# dimmer_sensor.net
KiCad netlist of a schematic drawn in Altium Designer
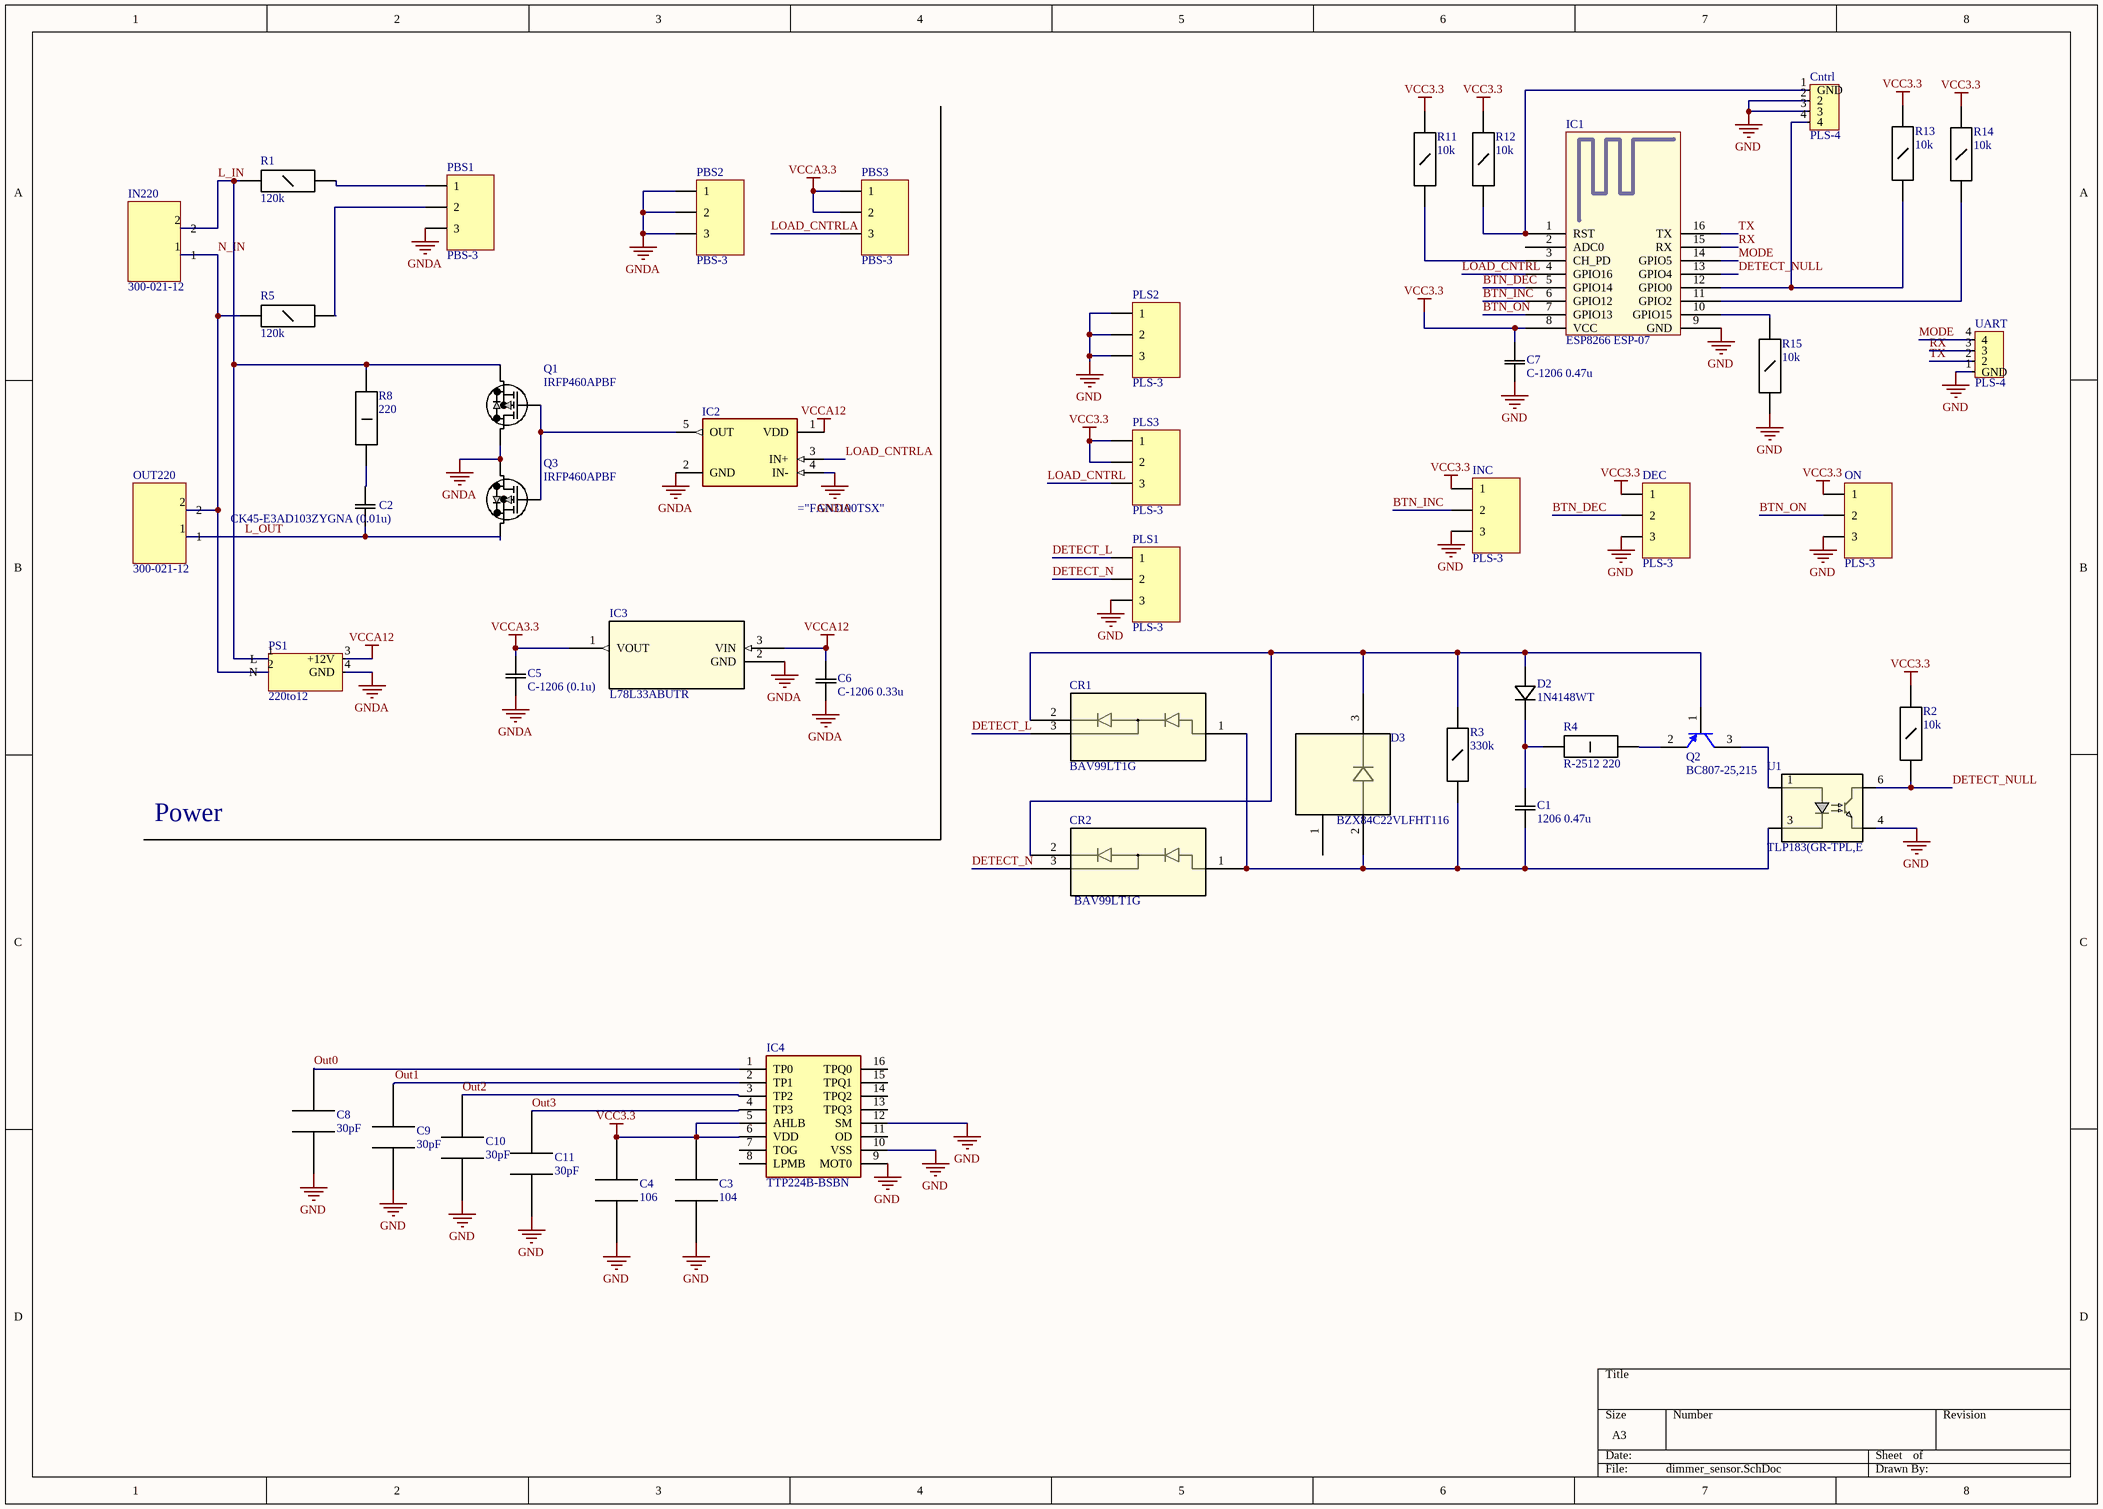
[diagram p0: dimmer_sensor.SchDoc]

(export (version "E")
  (design (tool "Eeschema 10.0.6"))
  (components
    (comp (ref "C1")
      (value "1206 0.47u")
      (footprint "CAP_X7R_1206_AVX")
      (description "No Description Available")
      (fields
        (field (name "MANUFACTURER_PART_NUMBER") "12061C104KAT2A")
        (field (name "COPYRIGHT") "Copyright (C) 2018 Accelerated Designs. All rights reserved")
      )
      (libsource (lib "diplom") (part "C-1206"))
    )
    (comp (ref "C2")
      (value "CK45-E3AD103ZYGNA (0.01u)")
      (footprint "CAP_CK45E3103_TDK")
      (description "No Description Available")
      (fields
        (field (name "MANUFACTURER_PART_NUMBER") "CK45-E3AD103ZYGNA")
        (field (name "COPYRIGHT") "Copyright (C) 2018 Accelerated Designs. All rights reserved")
      )
      (libsource (lib "diplom") (part "CK45-E3AD103ZYGNA"))
    )
    (comp (ref "C3")
      (value "104")
      (footprint "0805")
      (description "0805 ceramic capacitor")
      (libsource (lib "diplom") (part "C0805"))
    )
    (comp (ref "C4")
      (value "106")
      (footprint "0805")
      (description "0805 ceramic capacitor")
      (libsource (lib "diplom") (part "C0805"))
    )
    (comp (ref "C5")
      (value "C-1206 (0.1u)")
      (footprint "CAP_X7R_1206_AVX")
      (description "No Description Available")
      (fields
        (field (name "MANUFACTURER_PART_NUMBER") "12061C104KAT2A")
        (field (name "COPYRIGHT") "Copyright (C) 2018 Accelerated Designs. All rights reserved")
      )
      (libsource (lib "diplom") (part "C-1206"))
    )
    (comp (ref "C6")
      (value "C-1206 0.33u")
      (footprint "CAP_X7R_1206_AVX")
      (description "No Description Available")
      (fields
        (field (name "MANUFACTURER_PART_NUMBER") "12061C104KAT2A")
        (field (name "COPYRIGHT") "Copyright (C) 2018 Accelerated Designs. All rights reserved")
      )
      (libsource (lib "diplom") (part "C-1206"))
    )
    (comp (ref "C7")
      (value "C-1206 0.47u")
      (footprint "CAP_X7R_1206_AVX")
      (description "No Description Available")
      (fields
        (field (name "MANUFACTURER_PART_NUMBER") "12061C104KAT2A")
        (field (name "COPYRIGHT") "Copyright (C) 2018 Accelerated Designs. All rights reserved")
      )
      (libsource (lib "diplom") (part "C-1206"))
    )
    (comp (ref "C8")
      (value "30pF")
      (footprint "0805")
      (description "0805 ceramic capacitor")
      (libsource (lib "diplom") (part "C0805"))
    )
    (comp (ref "C9")
      (value "30pF")
      (footprint "0805")
      (description "0805 ceramic capacitor")
      (libsource (lib "diplom") (part "C0805"))
    )
    (comp (ref "C10")
      (value "30pF")
      (footprint "0805")
      (description "0805 ceramic capacitor")
      (libsource (lib "diplom") (part "C0805"))
    )
    (comp (ref "C11")
      (value "30pF")
      (footprint "0805")
      (description "0805 ceramic capacitor")
      (libsource (lib "diplom") (part "C0805"))
    )
    (comp (ref "Cntrl") (value "PLS-4") (footprint "PLS-4") (libsource (lib "diplom") (part "PLS-4")))
    (comp (ref "CR1")
      (value "BAV99LT1G")
      (footprint "SOT-23_TO-236_318-08_ONS")
      (description "No Description Available")
      (fields (field (name "COPYRIGHT") "Copyright (C) 2018 Accelerated Designs. All rights reserved"))
      (libsource (lib "diplom") (part "BAV99LT1G"))
    )
    (comp (ref "CR2")
      (value "BAV99LT1G")
      (footprint "SOT-23_TO-236_318-08_ONS")
      (description "No Description Available")
      (fields (field (name "COPYRIGHT") "Copyright (C) 2018 Accelerated Designs. All rights reserved"))
      (libsource (lib "diplom") (part "BAV99LT1G"))
    )
    (comp (ref "D2")
      (value "1N4148WT")
      (footprint "CR_SOD-523F_ONS")
      (description "No Description Available")
      (fields (field (name "COPYRIGHT") "Copyright (C) 2018 Accelerated Designs. All rights reserved"))
      (libsource (lib "diplom") (part "1N4148WT"))
    )
    (comp (ref "D3")
      (value "BZX84C22VLFHT116")
      (footprint "TRANS_BZX84_ROM")
      (description "No Description Available")
      (fields (field (name "COPYRIGHT") "Copyright (C) 2018 Accelerated Designs. All rights reserved"))
      (libsource (lib "diplom") (part "BZX84C22VLFHT116"))
    )
    (comp (ref "DEC") (value "PLS-3") (footprint "PLS-3") (libsource (lib "diplom") (part "PLS-3")))
    (comp (ref "IC1")
      (value "ESP8266 ESP-07")
      (footprint "ESP8266 ESP-07")
      (libsource (lib "diplom") (part "ESP8266 ESP-07"))
    )
    (comp (ref "IC2")
      (value "FAN3100TSX")
      (footprint "ON_Semi_527AH_0")
      (libsource (lib "diplom") (part "FAN3100TSX"))
    )
    (comp (ref "IC3")
      (value "L78L33ABUTR")
      (footprint "SOT-89_STM")
      (description "No Description Available")
      (fields (field (name "COPYRIGHT") "Copyright (C) 2018 Accelerated Designs. All rights reserved"))
      (libsource (lib "diplom") (part "L78L33ABUTR"))
    )
    (comp (ref "IC4")
      (value "TTP224B-BSBN")
      (footprint "SOP64P600X175-16N")
      (description "Integrated Circuit")
      (libsource (lib "diplom") (part "TTP224B-BSBN"))
    )
    (comp (ref "IN220")
      (value "300-021-12")
      (footprint "300-021-12")
      (libsource (lib "diplom") (part "300-021-12"))
    )
    (comp (ref "INC") (value "PLS-3") (footprint "PLS-3") (libsource (lib "diplom") (part "PLS-3")))
    (comp (ref "ON") (value "PLS-3") (footprint "PLS-3") (libsource (lib "diplom") (part "PLS-3")))
    (comp (ref "OUT220")
      (value "300-021-12")
      (footprint "300-021-12")
      (libsource (lib "diplom") (part "300-021-12"))
    )
    (comp (ref "PBS1") (value "PBS-3") (footprint "PBS-3") (libsource (lib "diplom") (part "PBS-3")))
    (comp (ref "PBS2") (value "PBS-3") (footprint "PBS-3") (libsource (lib "diplom") (part "PBS-3")))
    (comp (ref "PBS3") (value "PBS-3") (footprint "PBS-3") (libsource (lib "diplom") (part "PBS-3")))
    (comp (ref "PLS1") (value "PLS-3") (footprint "PLS-3") (libsource (lib "diplom") (part "PLS-3")))
    (comp (ref "PLS2") (value "PLS-3") (footprint "PLS-3") (libsource (lib "diplom") (part "PLS-3")))
    (comp (ref "PLS3") (value "PLS-3") (footprint "PLS-3") (libsource (lib "diplom") (part "PLS-3")))
    (comp (ref "PS1") (value "220to12") (footprint "220to12") (libsource (lib "diplom") (part "220to12")))
    (comp (ref "Q1")
      (value "IRFP460APBF")
      (footprint "TO-247AC_VIS")
      (description "No Description Available")
      (fields (field (name "COPYRIGHT") "Copyright (C) 2018 Accelerated Designs. All rights reserved"))
      (libsource (lib "diplom") (part "IRFP460APBF"))
    )
    (comp (ref "Q2")
      (value "BC807-25,215")
      (footprint "SOT23_BC807_NEX")
      (description "No Description Available")
      (fields (field (name "COPYRIGHT") "Copyright (C) 2016 Accelerated Designs. All rights reserved"))
      (libsource (lib "diplom") (part "BC807-25,215"))
    )
    (comp (ref "Q3")
      (value "IRFP460APBF")
      (footprint "TO-247AC_VIS")
      (description "No Description Available")
      (fields (field (name "COPYRIGHT") "Copyright (C) 2018 Accelerated Designs. All rights reserved"))
      (libsource (lib "diplom") (part "IRFP460APBF"))
    )
    (comp (ref "R1")
      (value "120k")
      (footprint "CAP_X7R_1206_AVX")
      (description "R-1206")
      (libsource (lib "diplom") (part "R-1206"))
    )
    (comp (ref "R2")
      (value "10k")
      (footprint "CAP_X7R_1206_AVX")
      (description "R-1206")
      (libsource (lib "diplom") (part "R-1206"))
    )
    (comp (ref "R3")
      (value "330k")
      (footprint "CAP_X7R_1206_AVX")
      (description "R-1206")
      (libsource (lib "diplom") (part "R-1206"))
    )
    (comp (ref "R4")
      (value "R-2512 220")
      (footprint "RES2512_TL_TYCO_TYC")
      (description "No Description Available")
      (fields
        (field (name "MANUFACTURER_PART_NUMBER") "TL3AR033F")
        (field (name "COPYRIGHT") "Copyright (C) 2018 Accelerated Designs. All rights reserved")
      )
      (libsource (lib "diplom") (part "R-2512"))
    )
    (comp (ref "R5")
      (value "120k")
      (footprint "CAP_X7R_1206_AVX")
      (description "R-1206")
      (libsource (lib "diplom") (part "R-1206"))
    )
    (comp (ref "R8")
      (value "220")
      (footprint "RES2512_TL_TYCO_TYC")
      (description "No Description Available")
      (fields
        (field (name "MANUFACTURER_PART_NUMBER") "TL3AR033F")
        (field (name "COPYRIGHT") "Copyright (C) 2018 Accelerated Designs. All rights reserved")
      )
      (libsource (lib "diplom") (part "R-2512"))
    )
    (comp (ref "R11")
      (value "10k")
      (footprint "CAP_X7R_1206_AVX")
      (description "R-1206")
      (libsource (lib "diplom") (part "R-1206"))
    )
    (comp (ref "R12")
      (value "10k")
      (footprint "CAP_X7R_1206_AVX")
      (description "R-1206")
      (libsource (lib "diplom") (part "R-1206"))
    )
    (comp (ref "R13")
      (value "10k")
      (footprint "CAP_X7R_1206_AVX")
      (description "R-1206")
      (libsource (lib "diplom") (part "R-1206"))
    )
    (comp (ref "R14")
      (value "10k")
      (footprint "CAP_X7R_1206_AVX")
      (description "R-1206")
      (libsource (lib "diplom") (part "R-1206"))
    )
    (comp (ref "R15")
      (value "10k")
      (footprint "CAP_X7R_1206_AVX")
      (description "R-1206")
      (libsource (lib "diplom") (part "R-1206"))
    )
    (comp (ref "U1")
      (value "TLP183(GR-TPL,E")
      (footprint "4pin SO6_TOS")
      (description "No Description Available")
      (fields (field (name "COPYRIGHT") "Copyright (C) 2018 Accelerated Designs. All rights reserved"))
      (libsource (lib "diplom") (part "TLP183(GR-TPL,E"))
    )
    (comp (ref "UART") (value "PLS-4") (footprint "PLS-4") (libsource (lib "") (part "PLS-4_1")))
  )
  (nets
    (net (code "1") (name "/BTN_DEC") (class "Default")
      (node (ref "DEC") (pin "2") (pinfunction "2_2") (pintype "passive"))
      (node (ref "IC1") (pin "5") (pinfunction "GPIO14_5") (pintype "passive"))
    )
    (net (code "2") (name "/BTN_INC") (class "Default")
      (node (ref "IC1") (pin "6") (pinfunction "GPIO12_6") (pintype "passive"))
      (node (ref "INC") (pin "2") (pinfunction "2_2") (pintype "passive"))
    )
    (net (code "3") (name "/BTN_ON") (class "Default")
      (node (ref "IC1") (pin "7") (pinfunction "GPIO13_7") (pintype "passive"))
      (node (ref "ON") (pin "2") (pinfunction "2_2") (pintype "passive"))
    )
    (net (code "4") (name "/DETECT_L") (class "Default")
      (node (ref "CR1") (pin "3") (pinfunction "3_3") (pintype "passive"))
      (node (ref "PLS1") (pin "1") (pinfunction "1_1") (pintype "passive"))
    )
    (net (code "5") (name "/DETECT_N") (class "Default")
      (node (ref "CR2") (pin "3") (pinfunction "3_3") (pintype "passive"))
      (node (ref "PLS1") (pin "2") (pinfunction "2_2") (pintype "passive"))
    )
    (net (code "6") (name "/DETECT_NULL") (class "Default")
      (node (ref "IC1") (pin "13") (pinfunction "GPIO4_13") (pintype "passive"))
      (node (ref "R2") (pin "1") (pinfunction "1_1") (pintype "passive"))
      (node (ref "U1") (pin "6") (pinfunction "6_6") (pintype "passive"))
    )
    (net (code "7") (name "/LOAD_CNTRL") (class "Default")
      (node (ref "IC1") (pin "4") (pinfunction "GPIO16_4") (pintype "passive"))
      (node (ref "PLS3") (pin "3") (pinfunction "3_3") (pintype "passive"))
    )
    (net (code "8") (name "/LOAD_CNTRLA") (class "Default")
      (node (ref "IC2") (pin "3") (pinfunction "IN+_3") (pintype "input"))
      (node (ref "PBS3") (pin "3") (pinfunction "3_3") (pintype "passive"))
    )
    (net (code "9") (name "/L_IN") (class "Default")
      (node (ref "IN220") (pin "2") (pinfunction "2_2") (pintype "passive"))
      (node (ref "PS1") (pin "1") (pinfunction "L_1") (pintype "passive"))
      (node (ref "Q1") (pin "3") (pinfunction "S_3") (pintype "passive"))
      (node (ref "R1") (pin "1") (pinfunction "1_1") (pintype "passive"))
      (node (ref "R8") (pin "2") (pinfunction "2_2") (pintype "passive"))
    )
    (net (code "10") (name "/L_OUT") (class "Default")
      (node (ref "C2") (pin "1") (pinfunction "1_1") (pintype "passive"))
      (node (ref "OUT220") (pin "1") (pinfunction "1_1") (pintype "passive"))
      (node (ref "Q3") (pin "3") (pinfunction "S_3") (pintype "passive"))
    )
    (net (code "11") (name "/MODE") (class "Default")
      (node (ref "IC1") (pin "14") (pinfunction "GPIO5_14") (pintype "passive"))
      (node (ref "UART") (pin "4") (pinfunction "4_4") (pintype "passive"))
    )
    (net (code "12") (name "/N_IN") (class "Default")
      (node (ref "IN220") (pin "1") (pinfunction "1_1") (pintype "passive"))
      (node (ref "OUT220") (pin "2") (pinfunction "2_2") (pintype "passive"))
      (node (ref "PS1") (pin "2") (pinfunction "N_2") (pintype "passive"))
      (node (ref "R5") (pin "1") (pinfunction "1_1") (pintype "passive"))
    )
    (net (code "13") (name "/Out0") (class "Default")
      (node (ref "C8") (pin "2") (pinfunction "2_2") (pintype "passive"))
      (node (ref "IC4") (pin "1") (pinfunction "TP0_1") (pintype "passive"))
    )
    (net (code "14") (name "/Out1") (class "Default")
      (node (ref "C9") (pin "2") (pinfunction "2_2") (pintype "passive"))
      (node (ref "IC4") (pin "2") (pinfunction "TP1_2") (pintype "passive"))
    )
    (net (code "15") (name "/Out2") (class "Default")
      (node (ref "C10") (pin "2") (pinfunction "2_2") (pintype "passive"))
      (node (ref "IC4") (pin "3") (pinfunction "TP2_3") (pintype "passive"))
    )
    (net (code "16") (name "/Out3") (class "Default")
      (node (ref "C11") (pin "2") (pinfunction "2_2") (pintype "passive"))
      (node (ref "IC4") (pin "4") (pinfunction "TP3_4") (pintype "passive"))
    )
    (net (code "17") (name "/RX") (class "Default")
      (node (ref "IC1") (pin "15") (pinfunction "RX_15") (pintype "passive"))
      (node (ref "UART") (pin "3") (pinfunction "3_3") (pintype "passive"))
    )
    (net (code "18") (name "/TX") (class "Default")
      (node (ref "IC1") (pin "16") (pinfunction "TX_16") (pintype "passive"))
      (node (ref "UART") (pin "2") (pinfunction "2_2") (pintype "passive"))
    )
    (net (code "19") (name "GND") (class "Default")
      (node (ref "C10") (pin "1") (pinfunction "1_1") (pintype "passive"))
      (node (ref "C11") (pin "1") (pinfunction "1_1") (pintype "passive"))
      (node (ref "C3") (pin "1") (pinfunction "1_1") (pintype "passive"))
      (node (ref "C4") (pin "1") (pinfunction "1_1") (pintype "passive"))
      (node (ref "C7") (pin "1") (pinfunction "1_1") (pintype "passive"))
      (node (ref "C8") (pin "1") (pinfunction "1_1") (pintype "passive"))
      (node (ref "C9") (pin "1") (pinfunction "1_1") (pintype "passive"))
      (node (ref "Cntrl") (pin "2") (pinfunction "2_2") (pintype "passive"))
      (node (ref "Cntrl") (pin "3") (pinfunction "3_3") (pintype "passive"))
      (node (ref "DEC") (pin "3") (pinfunction "3_3") (pintype "passive"))
      (node (ref "IC1") (pin "9") (pinfunction "GND_9") (pintype "passive"))
      (node (ref "IC4") (pin "10") (pinfunction "VSS_10") (pintype "passive"))
      (node (ref "IC4") (pin "12") (pinfunction "SM_12") (pintype "passive"))
      (node (ref "IC4") (pin "9") (pinfunction "MOT0_9") (pintype "passive"))
      (node (ref "INC") (pin "3") (pinfunction "3_3") (pintype "passive"))
      (node (ref "ON") (pin "3") (pinfunction "3_3") (pintype "passive"))
      (node (ref "PLS1") (pin "3") (pinfunction "3_3") (pintype "passive"))
      (node (ref "PLS2") (pin "1") (pinfunction "1_1") (pintype "passive"))
      (node (ref "PLS2") (pin "2") (pinfunction "2_2") (pintype "passive"))
      (node (ref "PLS2") (pin "3") (pinfunction "3_3") (pintype "passive"))
      (node (ref "R15") (pin "1") (pinfunction "1_1") (pintype "passive"))
      (node (ref "U1") (pin "4") (pinfunction "4_4") (pintype "passive"))
      (node (ref "UART") (pin "1") (pinfunction "GND_1") (pintype "passive"))
    )
    (net (code "20") (name "GNDA") (class "Default")
      (node (ref "C5") (pin "1") (pinfunction "1_1") (pintype "passive"))
      (node (ref "C6") (pin "1") (pinfunction "1_1") (pintype "passive"))
      (node (ref "IC2") (pin "2") (pinfunction "GND_2") (pintype "power_in"))
      (node (ref "IC2") (pin "4") (pinfunction "IN-_4") (pintype "input"))
      (node (ref "IC3") (pin "2") (pinfunction "GND_2") (pintype "passive"))
      (node (ref "PBS1") (pin "3") (pinfunction "3_3") (pintype "passive"))
      (node (ref "PBS2") (pin "1") (pinfunction "1_1") (pintype "passive"))
      (node (ref "PBS2") (pin "2") (pinfunction "2_2") (pintype "passive"))
      (node (ref "PBS2") (pin "3") (pinfunction "3_3") (pintype "passive"))
      (node (ref "PS1") (pin "4") (pinfunction "GND_4") (pintype "passive"))
      (node (ref "Q1") (pin "2") (pinfunction "D_2") (pintype "passive"))
      (node (ref "Q3") (pin "2") (pinfunction "D_2") (pintype "passive"))
    )
    (net (code "21") (name "Net-(C1-Pad2)") (class "Default")
      (node (ref "C1") (pin "2") (pinfunction "2_2") (pintype "passive"))
      (node (ref "D2") (pin "1") (pinfunction "1_1") (pintype "passive"))
      (node (ref "R4") (pin "1") (pinfunction "1_1") (pintype "passive"))
    )
    (net (code "22") (name "Net-(C2-Pad2)") (class "Default")
      (node (ref "C2") (pin "2") (pinfunction "2_2") (pintype "passive"))
      (node (ref "R8") (pin "1") (pinfunction "1_1") (pintype "passive"))
    )
    (net (code "23") (name "Net-(Cntrl-GND)") (class "Default")
      (node (ref "Cntrl") (pin "1") (pinfunction "GND_1") (pintype "passive"))
      (node (ref "IC1") (pin "1") (pinfunction "RST_1") (pintype "power_in"))
      (node (ref "R12") (pin "1") (pinfunction "1_1") (pintype "passive"))
    )
    (net (code "24") (name "Net-(D3-1)") (class "Default")
      (node (ref "C1") (pin "1") (pinfunction "1_1") (pintype "passive"))
      (node (ref "CR1") (pin "1") (pinfunction "1_1") (pintype "passive"))
      (node (ref "CR2") (pin "1") (pinfunction "1_1") (pintype "passive"))
      (node (ref "D3") (pin "2") (pinfunction "1_2") (pintype "passive"))
      (node (ref "R3") (pin "1") (pinfunction "1_1") (pintype "passive"))
      (node (ref "U1") (pin "3") (pinfunction "3_3") (pintype "passive"))
    )
    (net (code "25") (name "Net-(IC1-CH_PD)") (class "Default")
      (node (ref "IC1") (pin "3") (pinfunction "CH_PD_3") (pintype "passive"))
      (node (ref "R11") (pin "1") (pinfunction "1_1") (pintype "passive"))
    )
    (net (code "26") (name "Net-(IC1-GPIO0)") (class "Default")
      (node (ref "Cntrl") (pin "4") (pinfunction "4_4") (pintype "passive"))
      (node (ref "IC1") (pin "12") (pinfunction "GPIO0_12") (pintype "passive"))
      (node (ref "R13") (pin "1") (pinfunction "1_1") (pintype "passive"))
    )
    (net (code "27") (name "Net-(IC1-GPIO2)") (class "Default")
      (node (ref "IC1") (pin "11") (pinfunction "GPIO2_11") (pintype "passive"))
      (node (ref "R14") (pin "1") (pinfunction "1_1") (pintype "passive"))
    )
    (net (code "28") (name "Net-(IC1-GPIO15)") (class "Default")
      (node (ref "IC1") (pin "10") (pinfunction "GPIO15_10") (pintype "passive"))
      (node (ref "R15") (pin "2") (pinfunction "2_2") (pintype "passive"))
    )
    (net (code "29") (name "Net-(IC2-OUT)") (class "Default")
      (node (ref "IC2") (pin "5") (pinfunction "OUT_5") (pintype "output"))
      (node (ref "Q1") (pin "1") (pinfunction "G_1") (pintype "passive"))
      (node (ref "Q3") (pin "1") (pinfunction "G_1") (pintype "passive"))
    )
    (net (code "30") (name "Net-(PBS1-Pad1)") (class "Default")
      (node (ref "PBS1") (pin "1") (pinfunction "1_1") (pintype "passive"))
      (node (ref "R1") (pin "2") (pinfunction "2_2") (pintype "passive"))
    )
    (net (code "31") (name "Net-(PBS1-Pad2)") (class "Default")
      (node (ref "PBS1") (pin "2") (pinfunction "2_2") (pintype "passive"))
      (node (ref "R5") (pin "2") (pinfunction "2_2") (pintype "passive"))
    )
    (net (code "32") (name "Net-(Q2-B)") (class "Default")
      (node (ref "CR1") (pin "2") (pinfunction "2_2") (pintype "passive"))
      (node (ref "CR2") (pin "2") (pinfunction "2_2") (pintype "passive"))
      (node (ref "D2") (pin "2") (pinfunction "2_2") (pintype "passive"))
      (node (ref "D3") (pin "3") (pinfunction "3_3") (pintype "passive"))
      (node (ref "Q2") (pin "1") (pinfunction "B_1") (pintype "passive"))
      (node (ref "R3") (pin "2") (pinfunction "2_2") (pintype "passive"))
    )
    (net (code "33") (name "Net-(Q2-C)") (class "Default")
      (node (ref "Q2") (pin "3") (pinfunction "C_3") (pintype "passive"))
      (node (ref "U1") (pin "1") (pinfunction "1_1") (pintype "passive"))
    )
    (net (code "34") (name "Net-(Q2-Pad2)") (class "Default")
      (node (ref "Q2") (pin "2") (pintype "passive"))
      (node (ref "R4") (pin "2") (pinfunction "2_2") (pintype "passive"))
    )
    (net (code "35") (name "VCC3.3") (class "Default")
      (node (ref "C3") (pin "2") (pinfunction "2_2") (pintype "passive"))
      (node (ref "C4") (pin "2") (pinfunction "2_2") (pintype "passive"))
      (node (ref "C7") (pin "2") (pinfunction "2_2") (pintype "passive"))
      (node (ref "DEC") (pin "1") (pinfunction "1_1") (pintype "passive"))
      (node (ref "IC1") (pin "8") (pinfunction "VCC_8") (pintype "passive"))
      (node (ref "IC4") (pin "5") (pinfunction "AHLB_5") (pintype "passive"))
      (node (ref "IC4") (pin "6") (pinfunction "VDD_6") (pintype "passive"))
      (node (ref "INC") (pin "1") (pinfunction "1_1") (pintype "passive"))
      (node (ref "ON") (pin "1") (pinfunction "1_1") (pintype "passive"))
      (node (ref "PLS3") (pin "1") (pinfunction "1_1") (pintype "passive"))
      (node (ref "PLS3") (pin "2") (pinfunction "2_2") (pintype "passive"))
      (node (ref "R11") (pin "2") (pinfunction "2_2") (pintype "passive"))
      (node (ref "R12") (pin "2") (pinfunction "2_2") (pintype "passive"))
      (node (ref "R13") (pin "2") (pinfunction "2_2") (pintype "passive"))
      (node (ref "R14") (pin "2") (pinfunction "2_2") (pintype "passive"))
      (node (ref "R2") (pin "2") (pinfunction "2_2") (pintype "passive"))
    )
    (net (code "36") (name "VCCA3.3") (class "Default")
      (node (ref "C5") (pin "2") (pinfunction "2_2") (pintype "passive"))
      (node (ref "IC3") (pin "1") (pinfunction "VOUT_1") (pintype "output"))
      (node (ref "PBS3") (pin "1") (pinfunction "1_1") (pintype "passive"))
      (node (ref "PBS3") (pin "2") (pinfunction "2_2") (pintype "passive"))
    )
    (net (code "37") (name "VCCA12") (class "Default")
      (node (ref "C6") (pin "2") (pinfunction "2_2") (pintype "passive"))
      (node (ref "IC2") (pin "1") (pinfunction "VDD_1") (pintype "power_in"))
      (node (ref "IC3") (pin "3") (pinfunction "VIN_3") (pintype "input"))
      (node (ref "PS1") (pin "3") (pinfunction "+12V_3") (pintype "passive"))
    )
    (net (code "38") (name "unconnected-(D3-2-Pad1)") (class "Default")
      (node (ref "D3") (pin "1") (pinfunction "2_1") (pintype "passive"))
    )
    (net (code "39") (name "unconnected-(IC1-ADC0-Pad2)") (class "Default")
      (node (ref "IC1") (pin "2") (pinfunction "ADC0_2") (pintype "passive"))
    )
    (net (code "40") (name "unconnected-(IC4-LPMB-Pad8)") (class "Default")
      (node (ref "IC4") (pin "8") (pinfunction "LPMB_8") (pintype "passive"))
    )
    (net (code "41") (name "unconnected-(IC4-OD-Pad11)") (class "Default")
      (node (ref "IC4") (pin "11") (pinfunction "OD_11") (pintype "passive"))
    )
    (net (code "42") (name "unconnected-(IC4-TOG-Pad7)") (class "Default")
      (node (ref "IC4") (pin "7") (pinfunction "TOG_7") (pintype "passive"))
    )
    (net (code "43") (name "unconnected-(IC4-TPQ0-Pad16)") (class "Default")
      (node (ref "IC4") (pin "16") (pinfunction "TPQ0_16") (pintype "passive"))
    )
    (net (code "44") (name "unconnected-(IC4-TPQ1-Pad15)") (class "Default")
      (node (ref "IC4") (pin "15") (pinfunction "TPQ1_15") (pintype "passive"))
    )
    (net (code "45") (name "unconnected-(IC4-TPQ2-Pad14)") (class "Default")
      (node (ref "IC4") (pin "14") (pinfunction "TPQ2_14") (pintype "passive"))
    )
    (net (code "46") (name "unconnected-(IC4-TPQ3-Pad13)") (class "Default")
      (node (ref "IC4") (pin "13") (pinfunction "TPQ3_13") (pintype "passive"))
    )
  )
)
